# bbbcape.net
KiCad netlist of a schematic drawn in EAGLE
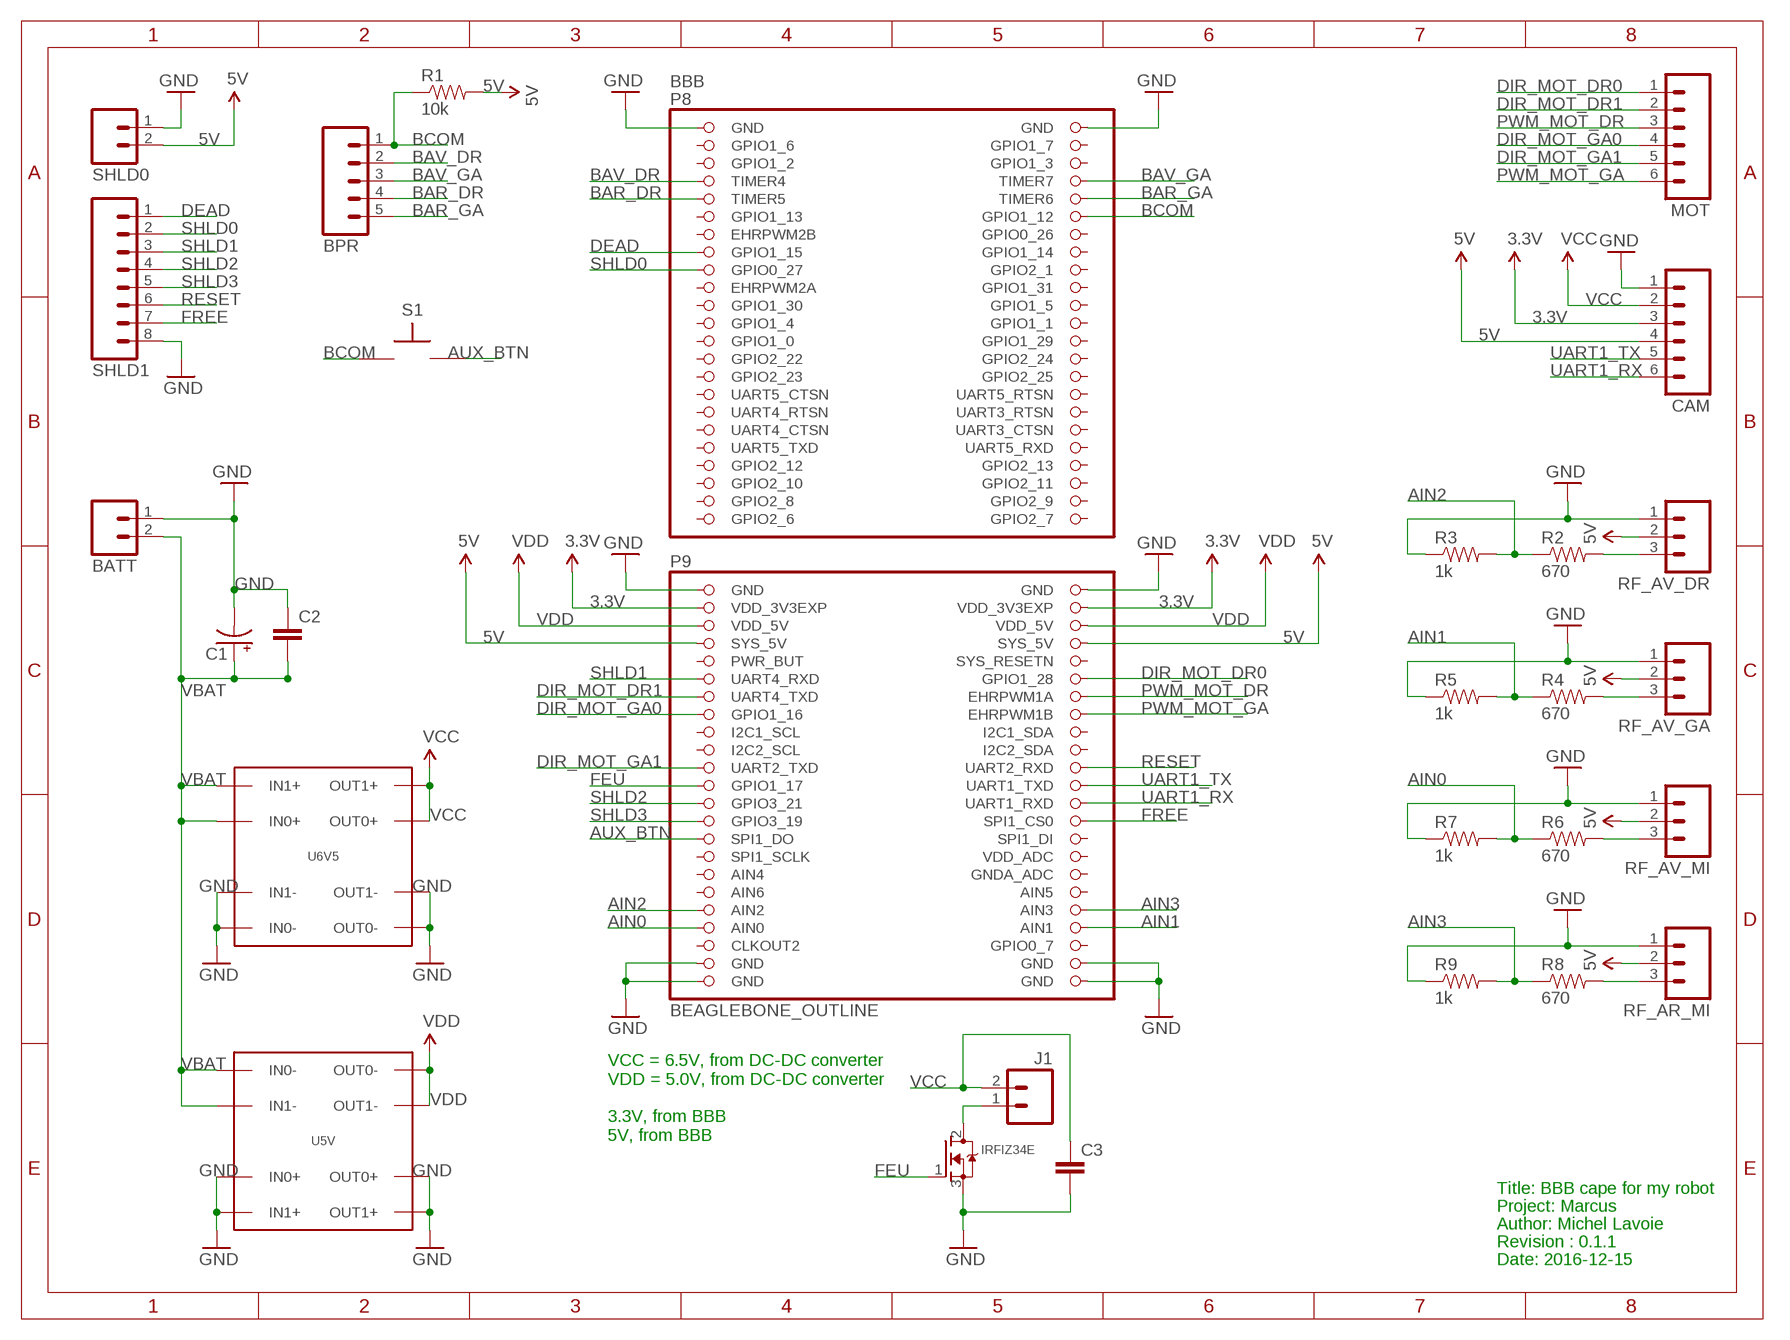
[diagram p0: schematic, sheet 1]

(export (version "E")
  (design (tool "Eeschema 10.0.6"))
  (components
    (comp (ref "BATT")
      (value "M02PTH")
      (footprint "eagle-import:1X02")
      (libsource (lib "eagle-import") (part "M02PTH"))
    )
    (comp (ref "BBB")
      (value "BEAGLEBONE_OUTLINE")
      (footprint "eagle-import:BEAGLEBONE_SHIELD")
      (libsource (lib "eagle-import") (part "BEAGLEBONE_OUTLINE"))
    )
    (comp (ref "BPR")
      (value "M05PTH")
      (footprint "eagle-import:1X05")
      (libsource (lib "eagle-import") (part "M05PTH"))
    )
    (comp (ref "C1")
      (value "100UF-25V-20%(PTH)")
      (footprint "eagle-import:CPOL-RADIAL-100UF-25V")
      (libsource (lib "eagle-import") (part "100UF-25V-20%(PTH)"))
    )
    (comp (ref "C2")
      (value "0.1UF-50V-20%(PTH)KIT-EZ")
      (footprint "eagle-import:CAP-PTH-SMALL-KIT")
      (libsource (lib "eagle-import") (part "0.1UF-50V-20%(PTH)KIT-EZ"))
    )
    (comp (ref "C3")
      (value "0.1UF-50V-20%(PTH)KIT-EZ")
      (footprint "eagle-import:CAP-PTH-SMALL-KIT")
      (libsource (lib "eagle-import") (part "0.1UF-50V-20%(PTH)KIT-EZ"))
    )
    (comp (ref "CAM")
      (value "M06SILK_FEMALE_PTH")
      (footprint "eagle-import:1X06")
      (libsource (lib "eagle-import") (part "M06SILK_FEMALE_PTH"))
    )
    (comp (ref "IRFIZ34E")
      (value "MOSFET-NGDS_TO220V")
      (footprint "eagle-import:TO220V")
      (libsource (lib "eagle-import") (part "MOSFET-NGDS_TO220V"))
    )
    (comp (ref "J1")
      (value "M02PTH")
      (footprint "eagle-import:1X02")
      (libsource (lib "eagle-import") (part "M02PTH"))
    )
    (comp (ref "MOT")
      (value "M06SILK_FEMALE_PTH")
      (footprint "eagle-import:1X06")
      (libsource (lib "eagle-import") (part "M06SILK_FEMALE_PTH"))
    )
    (comp (ref "R1")
      (value "10k")
      (footprint "eagle-import:AXIAL-0.3")
      (libsource (lib "eagle-import") (part "RESISTORAXIAL-0.3"))
    )
    (comp (ref "R2")
      (value "670")
      (footprint "eagle-import:AXIAL-0.3")
      (libsource (lib "eagle-import") (part "RESISTORAXIAL-0.3"))
    )
    (comp (ref "R3")
      (value "1k")
      (footprint "eagle-import:AXIAL-0.3")
      (libsource (lib "eagle-import") (part "RESISTORAXIAL-0.3"))
    )
    (comp (ref "R4")
      (value "670")
      (footprint "eagle-import:AXIAL-0.3")
      (libsource (lib "eagle-import") (part "RESISTORAXIAL-0.3"))
    )
    (comp (ref "R5")
      (value "1k")
      (footprint "eagle-import:AXIAL-0.3")
      (libsource (lib "eagle-import") (part "RESISTORAXIAL-0.3"))
    )
    (comp (ref "R6")
      (value "670")
      (footprint "eagle-import:AXIAL-0.3")
      (libsource (lib "eagle-import") (part "RESISTORAXIAL-0.3"))
    )
    (comp (ref "R7")
      (value "1k")
      (footprint "eagle-import:AXIAL-0.3")
      (libsource (lib "eagle-import") (part "RESISTORAXIAL-0.3"))
    )
    (comp (ref "R8")
      (value "670")
      (footprint "eagle-import:AXIAL-0.3")
      (libsource (lib "eagle-import") (part "RESISTORAXIAL-0.3"))
    )
    (comp (ref "R9")
      (value "1k")
      (footprint "eagle-import:AXIAL-0.3")
      (libsource (lib "eagle-import") (part "RESISTORAXIAL-0.3"))
    )
    (comp (ref "RF_AR_MI")
      (value "M03PTH")
      (footprint "eagle-import:1X03")
      (libsource (lib "eagle-import") (part "M03PTH"))
    )
    (comp (ref "RF_AV_DR")
      (value "M03PTH")
      (footprint "eagle-import:1X03")
      (libsource (lib "eagle-import") (part "M03PTH"))
    )
    (comp (ref "RF_AV_GA")
      (value "M03PTH")
      (footprint "eagle-import:1X03")
      (libsource (lib "eagle-import") (part "M03PTH"))
    )
    (comp (ref "RF_AV_MI")
      (value "M03PTH")
      (footprint "eagle-import:1X03")
      (libsource (lib "eagle-import") (part "M03PTH"))
    )
    (comp (ref "S1")
      (value "TACTILE-SPST-6MM-SLIM")
      (footprint "eagle-import:6MM-SLIM")
      (libsource (lib "eagle-import") (part "TACTILE-SPST-6MM-SLIM"))
    )
    (comp (ref "SHLD0")
      (value "M02PTH")
      (footprint "eagle-import:1X02")
      (libsource (lib "eagle-import") (part "M02PTH"))
    )
    (comp (ref "SHLD1")
      (value "M08")
      (footprint "eagle-import:1X08_ROUND")
      (libsource (lib "eagle-import") (part "M08"))
    )
    (comp (ref "U5V")
      (value "SEEED-MP1584")
      (footprint "eagle-import:SEEED-MP1584")
      (libsource (lib "eagle-import") (part "SEEED-MP1584"))
    )
    (comp (ref "U6V5")
      (value "SEEED-MP1584")
      (footprint "eagle-import:SEEED-MP1584")
      (libsource (lib "eagle-import") (part "SEEED-MP1584"))
    )
  )
  (nets
    (net (code "1") (name "/AIN0") (class "Default")
      (node (ref "BBB") (pin "85") (pinfunction "AIN0_85") (pintype "power_in"))
      (node (ref "R6") (pin "P$1") (pinfunction "1_P$1") (pintype "passive"))
      (node (ref "R7") (pin "P$2") (pinfunction "2_P$2") (pintype "passive"))
    )
    (net (code "2") (name "/AIN1") (class "Default")
      (node (ref "BBB") (pin "86") (pinfunction "AIN1_86") (pintype "passive"))
      (node (ref "R4") (pin "P$1") (pinfunction "1_P$1") (pintype "passive"))
      (node (ref "R5") (pin "P$2") (pinfunction "2_P$2") (pintype "passive"))
    )
    (net (code "3") (name "/AIN2") (class "Default")
      (node (ref "BBB") (pin "83") (pinfunction "AIN2_83") (pintype "passive"))
      (node (ref "R2") (pin "P$1") (pinfunction "1_P$1") (pintype "passive"))
      (node (ref "R3") (pin "P$2") (pinfunction "2_P$2") (pintype "passive"))
    )
    (net (code "4") (name "/AIN3") (class "Default")
      (node (ref "BBB") (pin "84") (pinfunction "AIN3_84") (pintype "passive"))
      (node (ref "R8") (pin "P$1") (pinfunction "1_P$1") (pintype "passive"))
      (node (ref "R9") (pin "P$2") (pinfunction "2_P$2") (pintype "passive"))
    )
    (net (code "5") (name "/AUX_BTN") (class "Default")
      (node (ref "BBB") (pin "75") (pinfunction "SPI1_DO_75") (pintype "passive"))
      (node (ref "S1") (pin "P$2") (pinfunction "P$2_P$2") (pintype "bidirectional"))
    )
    (net (code "6") (name "/BAR_DR") (class "Default")
      (node (ref "BBB") (pin "9") (pinfunction "TIMER5_9") (pintype "passive"))
      (node (ref "BPR") (pin "4") (pinfunction "4_4") (pintype "passive"))
    )
    (net (code "7") (name "/BAR_GA") (class "Default")
      (node (ref "BBB") (pin "10") (pinfunction "TIMER6_10") (pintype "passive"))
      (node (ref "BPR") (pin "5") (pinfunction "5_5") (pintype "passive"))
    )
    (net (code "8") (name "/BAV_DR") (class "Default")
      (node (ref "BBB") (pin "7") (pinfunction "TIMER4_7") (pintype "passive"))
      (node (ref "BPR") (pin "2") (pinfunction "2_2") (pintype "passive"))
    )
    (net (code "9") (name "/BAV_GA") (class "Default")
      (node (ref "BBB") (pin "8") (pinfunction "TIMER7_8") (pintype "passive"))
      (node (ref "BPR") (pin "3") (pinfunction "3_3") (pintype "passive"))
    )
    (net (code "10") (name "/BCOM") (class "Default")
      (node (ref "BBB") (pin "12") (pinfunction "GPIO1_12_12") (pintype "passive"))
      (node (ref "BPR") (pin "1") (pinfunction "1_1") (pintype "passive"))
      (node (ref "R1") (pin "P$1") (pinfunction "1_P$1") (pintype "passive"))
      (node (ref "S1") (pin "P$1") (pinfunction "P$1_P$1") (pintype "bidirectional"))
    )
    (net (code "11") (name "/DEAD") (class "Default")
      (node (ref "BBB") (pin "15") (pinfunction "GPIO1_15_15") (pintype "passive"))
      (node (ref "SHLD1") (pin "1") (pinfunction "1_1") (pintype "passive"))
    )
    (net (code "12") (name "/DIR_MOT_DR0") (class "Default")
      (node (ref "BBB") (pin "58") (pinfunction "GPIO1_28_58") (pintype "passive"))
      (node (ref "MOT") (pin "1") (pinfunction "1_1") (pintype "passive"))
    )
    (net (code "13") (name "/DIR_MOT_DR1") (class "Default")
      (node (ref "BBB") (pin "59") (pinfunction "UART4_TXD_59") (pintype "passive"))
      (node (ref "MOT") (pin "2") (pinfunction "2_2") (pintype "passive"))
    )
    (net (code "14") (name "/DIR_MOT_GA0") (class "Default")
      (node (ref "BBB") (pin "61") (pinfunction "GPIO1_16_61") (pintype "passive"))
      (node (ref "MOT") (pin "4") (pinfunction "4_4") (pintype "passive"))
    )
    (net (code "15") (name "/DIR_MOT_GA1") (class "Default")
      (node (ref "BBB") (pin "67") (pinfunction "UART2_TXD_67") (pintype "passive"))
      (node (ref "MOT") (pin "5") (pinfunction "5_5") (pintype "passive"))
    )
    (net (code "16") (name "/FEU") (class "Default")
      (node (ref "BBB") (pin "69") (pinfunction "GPIO1_17_69") (pintype "passive"))
      (node (ref "IRFIZ34E") (pin "1") (pinfunction "G_1") (pintype "bidirectional"))
    )
    (net (code "17") (name "/FREE") (class "Default")
      (node (ref "BBB") (pin "74") (pinfunction "SPI1_CS0_74") (pintype "passive"))
      (node (ref "SHLD1") (pin "7") (pinfunction "7_7") (pintype "passive"))
    )
    (net (code "18") (name "/PWM_MOT_DR") (class "Default")
      (node (ref "BBB") (pin "60") (pinfunction "EHRPWM1A_60") (pintype "passive"))
      (node (ref "MOT") (pin "3") (pinfunction "3_3") (pintype "passive"))
    )
    (net (code "19") (name "/PWM_MOT_GA") (class "Default")
      (node (ref "BBB") (pin "62") (pinfunction "EHRPWM1B_62") (pintype "passive"))
      (node (ref "MOT") (pin "6") (pinfunction "6_6") (pintype "passive"))
    )
    (net (code "20") (name "/RESET") (class "Default")
      (node (ref "BBB") (pin "68") (pinfunction "UART2_RXD_68") (pintype "passive"))
      (node (ref "SHLD1") (pin "6") (pinfunction "6_6") (pintype "passive"))
    )
    (net (code "21") (name "/SHLD0") (class "Default")
      (node (ref "BBB") (pin "17") (pinfunction "GPIO0_27_17") (pintype "passive"))
      (node (ref "SHLD1") (pin "2") (pinfunction "2_2") (pintype "passive"))
    )
    (net (code "22") (name "/SHLD1") (class "Default")
      (node (ref "BBB") (pin "57") (pinfunction "UART4_RXD_57") (pintype "passive"))
      (node (ref "SHLD1") (pin "3") (pinfunction "3_3") (pintype "passive"))
    )
    (net (code "23") (name "/SHLD2") (class "Default")
      (node (ref "BBB") (pin "71") (pinfunction "GPIO3_21_71") (pintype "passive"))
      (node (ref "SHLD1") (pin "4") (pinfunction "4_4") (pintype "passive"))
    )
    (net (code "24") (name "/SHLD3") (class "Default")
      (node (ref "BBB") (pin "73") (pinfunction "GPIO3_19_73") (pintype "passive"))
      (node (ref "SHLD1") (pin "5") (pinfunction "5_5") (pintype "passive"))
    )
    (net (code "25") (name "/UART1_RX") (class "Default")
      (node (ref "BBB") (pin "72") (pinfunction "UART1_RXD_72") (pintype "passive"))
      (node (ref "CAM") (pin "6") (pinfunction "6_6") (pintype "passive"))
    )
    (net (code "26") (name "/UART1_TX") (class "Default")
      (node (ref "BBB") (pin "70") (pinfunction "UART1_TXD_70") (pintype "passive"))
      (node (ref "CAM") (pin "5") (pinfunction "5_5") (pintype "passive"))
    )
    (net (code "27") (name "/VBAT") (class "Default")
      (node (ref "BATT") (pin "2") (pinfunction "2_2") (pintype "passive"))
      (node (ref "C1") (pin "1") (pinfunction "+_1") (pintype "passive"))
      (node (ref "C2") (pin "2") (pinfunction "2_2") (pintype "passive"))
      (node (ref "U5V") (pin "IN0-") (pinfunction "IN0-_IN0-") (pintype "bidirectional"))
      (node (ref "U5V") (pin "IN1-") (pinfunction "IN1-_IN1-") (pintype "bidirectional"))
      (node (ref "U6V5") (pin "IN0+") (pinfunction "IN0+_IN0+") (pintype "bidirectional"))
      (node (ref "U6V5") (pin "IN1+") (pinfunction "IN1+_IN1+") (pintype "bidirectional"))
    )
    (net (code "28") (name "3.3V") (class "Default")
      (node (ref "BBB") (pin "49") (pinfunction "VDD_3V3EXP_49") (pintype "power_in"))
      (node (ref "BBB") (pin "50") (pinfunction "VDD_3V3EXP_50") (pintype "power_in"))
      (node (ref "CAM") (pin "3") (pinfunction "3_3") (pintype "passive"))
    )
    (net (code "29") (name "5V") (class "Default")
      (node (ref "BBB") (pin "53") (pinfunction "SYS_5V_53") (pintype "power_in"))
      (node (ref "BBB") (pin "54") (pinfunction "SYS_5V_54") (pintype "passive"))
      (node (ref "CAM") (pin "4") (pinfunction "4_4") (pintype "passive"))
      (node (ref "R1") (pin "P$2") (pinfunction "2_P$2") (pintype "passive"))
      (node (ref "RF_AR_MI") (pin "2") (pinfunction "2_2") (pintype "passive"))
      (node (ref "RF_AV_DR") (pin "2") (pinfunction "2_2") (pintype "passive"))
      (node (ref "RF_AV_GA") (pin "2") (pinfunction "2_2") (pintype "passive"))
      (node (ref "RF_AV_MI") (pin "2") (pinfunction "2_2") (pintype "passive"))
      (node (ref "SHLD0") (pin "2") (pinfunction "2_2") (pintype "passive"))
    )
    (net (code "30") (name "GND") (class "Default")
      (node (ref "BATT") (pin "1") (pinfunction "1_1") (pintype "passive"))
      (node (ref "BBB") (pin "1") (pinfunction "GND_1") (pintype "power_in"))
      (node (ref "BBB") (pin "2") (pinfunction "GND_2") (pintype "power_in"))
      (node (ref "BBB") (pin "47") (pinfunction "GND_47") (pintype "power_in"))
      (node (ref "BBB") (pin "48") (pinfunction "GND_48") (pintype "power_in"))
      (node (ref "BBB") (pin "89") (pinfunction "GND_89") (pintype "power_in"))
      (node (ref "BBB") (pin "90") (pinfunction "GND_90") (pintype "power_in"))
      (node (ref "BBB") (pin "91") (pinfunction "GND_91") (pintype "power_in"))
      (node (ref "BBB") (pin "92") (pinfunction "GND_92") (pintype "power_in"))
      (node (ref "C1") (pin "2") (pinfunction "-_2") (pintype "passive"))
      (node (ref "C2") (pin "1") (pinfunction "1_1") (pintype "passive"))
      (node (ref "C3") (pin "2") (pinfunction "2_2") (pintype "passive"))
      (node (ref "CAM") (pin "1") (pinfunction "1_1") (pintype "passive"))
      (node (ref "IRFIZ34E") (pin "3") (pinfunction "S_3") (pintype "bidirectional"))
      (node (ref "R3") (pin "P$1") (pinfunction "1_P$1") (pintype "passive"))
      (node (ref "R5") (pin "P$1") (pinfunction "1_P$1") (pintype "passive"))
      (node (ref "R7") (pin "P$1") (pinfunction "1_P$1") (pintype "passive"))
      (node (ref "R9") (pin "P$1") (pinfunction "1_P$1") (pintype "passive"))
      (node (ref "RF_AR_MI") (pin "1") (pinfunction "1_1") (pintype "passive"))
      (node (ref "RF_AV_DR") (pin "1") (pinfunction "1_1") (pintype "passive"))
      (node (ref "RF_AV_GA") (pin "1") (pinfunction "1_1") (pintype "passive"))
      (node (ref "RF_AV_MI") (pin "1") (pinfunction "1_1") (pintype "passive"))
      (node (ref "SHLD0") (pin "1") (pinfunction "1_1") (pintype "passive"))
      (node (ref "SHLD1") (pin "8") (pinfunction "8_8") (pintype "passive"))
      (node (ref "U5V") (pin "IN0+") (pinfunction "IN0+_IN0+") (pintype "bidirectional"))
      (node (ref "U5V") (pin "IN1+") (pinfunction "IN1+_IN1+") (pintype "bidirectional"))
      (node (ref "U5V") (pin "OUT0+") (pinfunction "OUT0+_OUT0+") (pintype "bidirectional"))
      (node (ref "U5V") (pin "OUT1+") (pinfunction "OUT1+_OUT1+") (pintype "bidirectional"))
      (node (ref "U6V5") (pin "IN0-") (pinfunction "IN0-_IN0-") (pintype "bidirectional"))
      (node (ref "U6V5") (pin "IN1-") (pinfunction "IN1-_IN1-") (pintype "bidirectional"))
      (node (ref "U6V5") (pin "OUT0-") (pinfunction "OUT0-_OUT0-") (pintype "bidirectional"))
      (node (ref "U6V5") (pin "OUT1-") (pinfunction "OUT1-_OUT1-") (pintype "bidirectional"))
    )
    (net (code "31") (name "Net-(IRFIZ34E-D)") (class "Default")
      (node (ref "IRFIZ34E") (pin "2") (pinfunction "D_2") (pintype "bidirectional"))
      (node (ref "J1") (pin "1") (pinfunction "1_1") (pintype "passive"))
    )
    (net (code "32") (name "Net-(R2-2)") (class "Default")
      (node (ref "R2") (pin "P$2") (pinfunction "2_P$2") (pintype "passive"))
      (node (ref "RF_AV_DR") (pin "3") (pinfunction "3_3") (pintype "passive"))
    )
    (net (code "33") (name "Net-(R4-2)") (class "Default")
      (node (ref "R4") (pin "P$2") (pinfunction "2_P$2") (pintype "passive"))
      (node (ref "RF_AV_GA") (pin "3") (pinfunction "3_3") (pintype "passive"))
    )
    (net (code "34") (name "Net-(R6-2)") (class "Default")
      (node (ref "R6") (pin "P$2") (pinfunction "2_P$2") (pintype "passive"))
      (node (ref "RF_AV_MI") (pin "3") (pinfunction "3_3") (pintype "passive"))
    )
    (net (code "35") (name "Net-(R8-2)") (class "Default")
      (node (ref "R8") (pin "P$2") (pinfunction "2_P$2") (pintype "passive"))
      (node (ref "RF_AR_MI") (pin "3") (pinfunction "3_3") (pintype "passive"))
    )
    (net (code "36") (name "VCC") (class "Default")
      (node (ref "C3") (pin "1") (pinfunction "1_1") (pintype "passive"))
      (node (ref "CAM") (pin "2") (pinfunction "2_2") (pintype "passive"))
      (node (ref "J1") (pin "2") (pinfunction "2_2") (pintype "passive"))
      (node (ref "U6V5") (pin "OUT0+") (pinfunction "OUT0+_OUT0+") (pintype "bidirectional"))
      (node (ref "U6V5") (pin "OUT1+") (pinfunction "OUT1+_OUT1+") (pintype "bidirectional"))
    )
    (net (code "37") (name "VDD") (class "Default")
      (node (ref "BBB") (pin "51") (pinfunction "VDD_5V_51") (pintype "power_in"))
      (node (ref "BBB") (pin "52") (pinfunction "VDD_5V_52") (pintype "power_in"))
      (node (ref "U5V") (pin "OUT0-") (pinfunction "OUT0-_OUT0-") (pintype "bidirectional"))
      (node (ref "U5V") (pin "OUT1-") (pinfunction "OUT1-_OUT1-") (pintype "bidirectional"))
    )
    (net (code "38") (name "unconnected-(BBB-AIN4-Pad79)") (class "Default")
      (node (ref "BBB") (pin "79") (pinfunction "AIN4_79") (pintype "passive"))
    )
    (net (code "39") (name "unconnected-(BBB-AIN5-Pad82)") (class "Default")
      (node (ref "BBB") (pin "82") (pinfunction "AIN5_82") (pintype "passive"))
    )
    (net (code "40") (name "unconnected-(BBB-AIN6-Pad81)") (class "Default")
      (node (ref "BBB") (pin "81") (pinfunction "AIN6_81") (pintype "passive"))
    )
    (net (code "41") (name "unconnected-(BBB-CLKOUT2-Pad87)") (class "Default")
      (node (ref "BBB") (pin "87") (pinfunction "CLKOUT2_87") (pintype "input"))
    )
    (net (code "42") (name "unconnected-(BBB-EHRPWM2A-Pad19)") (class "Default")
      (node (ref "BBB") (pin "19") (pinfunction "EHRPWM2A_19") (pintype "passive"))
    )
    (net (code "43") (name "unconnected-(BBB-EHRPWM2B-Pad13)") (class "Default")
      (node (ref "BBB") (pin "13") (pinfunction "EHRPWM2B_13") (pintype "passive"))
    )
    (net (code "44") (name "unconnected-(BBB-GNDA_ADC-Pad80)") (class "Default")
      (node (ref "BBB") (pin "80") (pinfunction "GNDA_ADC_80") (pintype "passive"))
    )
    (net (code "45") (name "unconnected-(BBB-GPIO0_7-Pad88)") (class "Default")
      (node (ref "BBB") (pin "88") (pinfunction "GPIO0_7_88") (pintype "passive"))
    )
    (net (code "46") (name "unconnected-(BBB-GPIO0_26-Pad14)") (class "Default")
      (node (ref "BBB") (pin "14") (pinfunction "GPIO0_26_14") (pintype "passive"))
    )
    (net (code "47") (name "unconnected-(BBB-GPIO1_0-Pad25)") (class "Default")
      (node (ref "BBB") (pin "25") (pinfunction "GPIO1_0_25") (pintype "passive"))
    )
    (net (code "48") (name "unconnected-(BBB-GPIO1_1-Pad24)") (class "Default")
      (node (ref "BBB") (pin "24") (pinfunction "GPIO1_1_24") (pintype "passive"))
    )
    (net (code "49") (name "unconnected-(BBB-GPIO1_2-Pad5)") (class "Default")
      (node (ref "BBB") (pin "5") (pinfunction "GPIO1_2_5") (pintype "passive"))
    )
    (net (code "50") (name "unconnected-(BBB-GPIO1_3-Pad6)") (class "Default")
      (node (ref "BBB") (pin "6") (pinfunction "GPIO1_3_6") (pintype "passive"))
    )
    (net (code "51") (name "unconnected-(BBB-GPIO1_4-Pad23)") (class "Default")
      (node (ref "BBB") (pin "23") (pinfunction "GPIO1_4_23") (pintype "passive"))
    )
    (net (code "52") (name "unconnected-(BBB-GPIO1_5-Pad22)") (class "Default")
      (node (ref "BBB") (pin "22") (pinfunction "GPIO1_5_22") (pintype "passive"))
    )
    (net (code "53") (name "unconnected-(BBB-GPIO1_6-Pad3)") (class "Default")
      (node (ref "BBB") (pin "3") (pinfunction "GPIO1_6_3") (pintype "passive"))
    )
    (net (code "54") (name "unconnected-(BBB-GPIO1_7-Pad4)") (class "Default")
      (node (ref "BBB") (pin "4") (pinfunction "GPIO1_7_4") (pintype "passive"))
    )
    (net (code "55") (name "unconnected-(BBB-GPIO1_13-Pad11)") (class "Default")
      (node (ref "BBB") (pin "11") (pinfunction "GPIO1_13_11") (pintype "passive"))
    )
    (net (code "56") (name "unconnected-(BBB-GPIO1_14-Pad16)") (class "Default")
      (node (ref "BBB") (pin "16") (pinfunction "GPIO1_14_16") (pintype "passive"))
    )
    (net (code "57") (name "unconnected-(BBB-GPIO1_29-Pad26)") (class "Default")
      (node (ref "BBB") (pin "26") (pinfunction "GPIO1_29_26") (pintype "passive"))
    )
    (net (code "58") (name "unconnected-(BBB-GPIO1_30-Pad21)") (class "Default")
      (node (ref "BBB") (pin "21") (pinfunction "GPIO1_30_21") (pintype "passive"))
    )
    (net (code "59") (name "unconnected-(BBB-GPIO1_31-Pad20)") (class "Default")
      (node (ref "BBB") (pin "20") (pinfunction "GPIO1_31_20") (pintype "passive"))
    )
    (net (code "60") (name "unconnected-(BBB-GPIO2_1-Pad18)") (class "Default")
      (node (ref "BBB") (pin "18") (pinfunction "GPIO2_1_18") (pintype "passive"))
    )
    (net (code "61") (name "unconnected-(BBB-GPIO2_6-Pad45)") (class "Default")
      (node (ref "BBB") (pin "45") (pinfunction "GPIO2_6_45") (pintype "passive"))
    )
    (net (code "62") (name "unconnected-(BBB-GPIO2_7-Pad46)") (class "Default")
      (node (ref "BBB") (pin "46") (pinfunction "GPIO2_7_46") (pintype "passive"))
    )
    (net (code "63") (name "unconnected-(BBB-GPIO2_8-Pad43)") (class "Default")
      (node (ref "BBB") (pin "43") (pinfunction "GPIO2_8_43") (pintype "passive"))
    )
    (net (code "64") (name "unconnected-(BBB-GPIO2_9-Pad44)") (class "Default")
      (node (ref "BBB") (pin "44") (pinfunction "GPIO2_9_44") (pintype "passive"))
    )
    (net (code "65") (name "unconnected-(BBB-GPIO2_10-Pad41)") (class "Default")
      (node (ref "BBB") (pin "41") (pinfunction "GPIO2_10_41") (pintype "passive"))
    )
    (net (code "66") (name "unconnected-(BBB-GPIO2_11-Pad42)") (class "Default")
      (node (ref "BBB") (pin "42") (pinfunction "GPIO2_11_42") (pintype "passive"))
    )
    (net (code "67") (name "unconnected-(BBB-GPIO2_12-Pad39)") (class "Default")
      (node (ref "BBB") (pin "39") (pinfunction "GPIO2_12_39") (pintype "passive"))
    )
    (net (code "68") (name "unconnected-(BBB-GPIO2_13-Pad40)") (class "Default")
      (node (ref "BBB") (pin "40") (pinfunction "GPIO2_13_40") (pintype "passive"))
    )
    (net (code "69") (name "unconnected-(BBB-GPIO2_22-Pad27)") (class "Default")
      (node (ref "BBB") (pin "27") (pinfunction "GPIO2_22_27") (pintype "passive"))
    )
    (net (code "70") (name "unconnected-(BBB-GPIO2_23-Pad29)") (class "Default")
      (node (ref "BBB") (pin "29") (pinfunction "GPIO2_23_29") (pintype "passive"))
    )
    (net (code "71") (name "unconnected-(BBB-GPIO2_24-Pad28)") (class "Default")
      (node (ref "BBB") (pin "28") (pinfunction "GPIO2_24_28") (pintype "passive"))
    )
    (net (code "72") (name "unconnected-(BBB-GPIO2_25-Pad30)") (class "Default")
      (node (ref "BBB") (pin "30") (pinfunction "GPIO2_25_30") (pintype "passive"))
    )
    (net (code "73") (name "unconnected-(BBB-I2C1_SCL-Pad63)") (class "Default")
      (node (ref "BBB") (pin "63") (pinfunction "I2C1_SCL_63") (pintype "passive"))
    )
    (net (code "74") (name "unconnected-(BBB-I2C1_SDA-Pad64)") (class "Default")
      (node (ref "BBB") (pin "64") (pinfunction "I2C1_SDA_64") (pintype "passive"))
    )
    (net (code "75") (name "unconnected-(BBB-I2C2_SCL-Pad65)") (class "Default")
      (node (ref "BBB") (pin "65") (pinfunction "I2C2_SCL_65") (pintype "passive"))
    )
    (net (code "76") (name "unconnected-(BBB-I2C2_SDA-Pad66)") (class "Default")
      (node (ref "BBB") (pin "66") (pinfunction "I2C2_SDA_66") (pintype "passive"))
    )
    (net (code "77") (name "unconnected-(BBB-PWR_BUT-Pad55)") (class "Default")
      (node (ref "BBB") (pin "55") (pinfunction "PWR_BUT_55") (pintype "passive"))
    )
    (net (code "78") (name "unconnected-(BBB-SPI1_DI-Pad76)") (class "Default")
      (node (ref "BBB") (pin "76") (pinfunction "SPI1_DI_76") (pintype "passive"))
    )
    (net (code "79") (name "unconnected-(BBB-SPI1_SCLK-Pad77)") (class "Default")
      (node (ref "BBB") (pin "77") (pinfunction "SPI1_SCLK_77") (pintype "passive"))
    )
    (net (code "80") (name "unconnected-(BBB-SYS_RESETN-Pad56)") (class "Default")
      (node (ref "BBB") (pin "56") (pinfunction "SYS_RESETN_56") (pintype "passive"))
    )
    (net (code "81") (name "unconnected-(BBB-UART3_CTSN-Pad36)") (class "Default")
      (node (ref "BBB") (pin "36") (pinfunction "UART3_CTSN_36") (pintype "passive"))
    )
    (net (code "82") (name "unconnected-(BBB-UART3_RTSN-Pad34)") (class "Default")
      (node (ref "BBB") (pin "34") (pinfunction "UART3_RTSN_34") (pintype "passive"))
    )
    (net (code "83") (name "unconnected-(BBB-UART4_CTSN-Pad35)") (class "Default")
      (node (ref "BBB") (pin "35") (pinfunction "UART4_CTSN_35") (pintype "passive"))
    )
    (net (code "84") (name "unconnected-(BBB-UART4_RTSN-Pad33)") (class "Default")
      (node (ref "BBB") (pin "33") (pinfunction "UART4_RTSN_33") (pintype "passive"))
    )
    (net (code "85") (name "unconnected-(BBB-UART5_CTSN-Pad31)") (class "Default")
      (node (ref "BBB") (pin "31") (pinfunction "UART5_CTSN_31") (pintype "passive"))
    )
    (net (code "86") (name "unconnected-(BBB-UART5_RTSN-Pad32)") (class "Default")
      (node (ref "BBB") (pin "32") (pinfunction "UART5_RTSN_32") (pintype "passive"))
    )
    (net (code "87") (name "unconnected-(BBB-UART5_RXD-Pad38)") (class "Default")
      (node (ref "BBB") (pin "38") (pinfunction "UART5_RXD_38") (pintype "passive"))
    )
    (net (code "88") (name "unconnected-(BBB-UART5_TXD-Pad37)") (class "Default")
      (node (ref "BBB") (pin "37") (pinfunction "UART5_TXD_37") (pintype "passive"))
    )
    (net (code "89") (name "unconnected-(BBB-VDD_ADC-Pad78)") (class "Default")
      (node (ref "BBB") (pin "78") (pinfunction "VDD_ADC_78") (pintype "passive"))
    )
  )
)
